# gauge-adapter.net
KiCad netlist of a schematic drawn in EAGLE
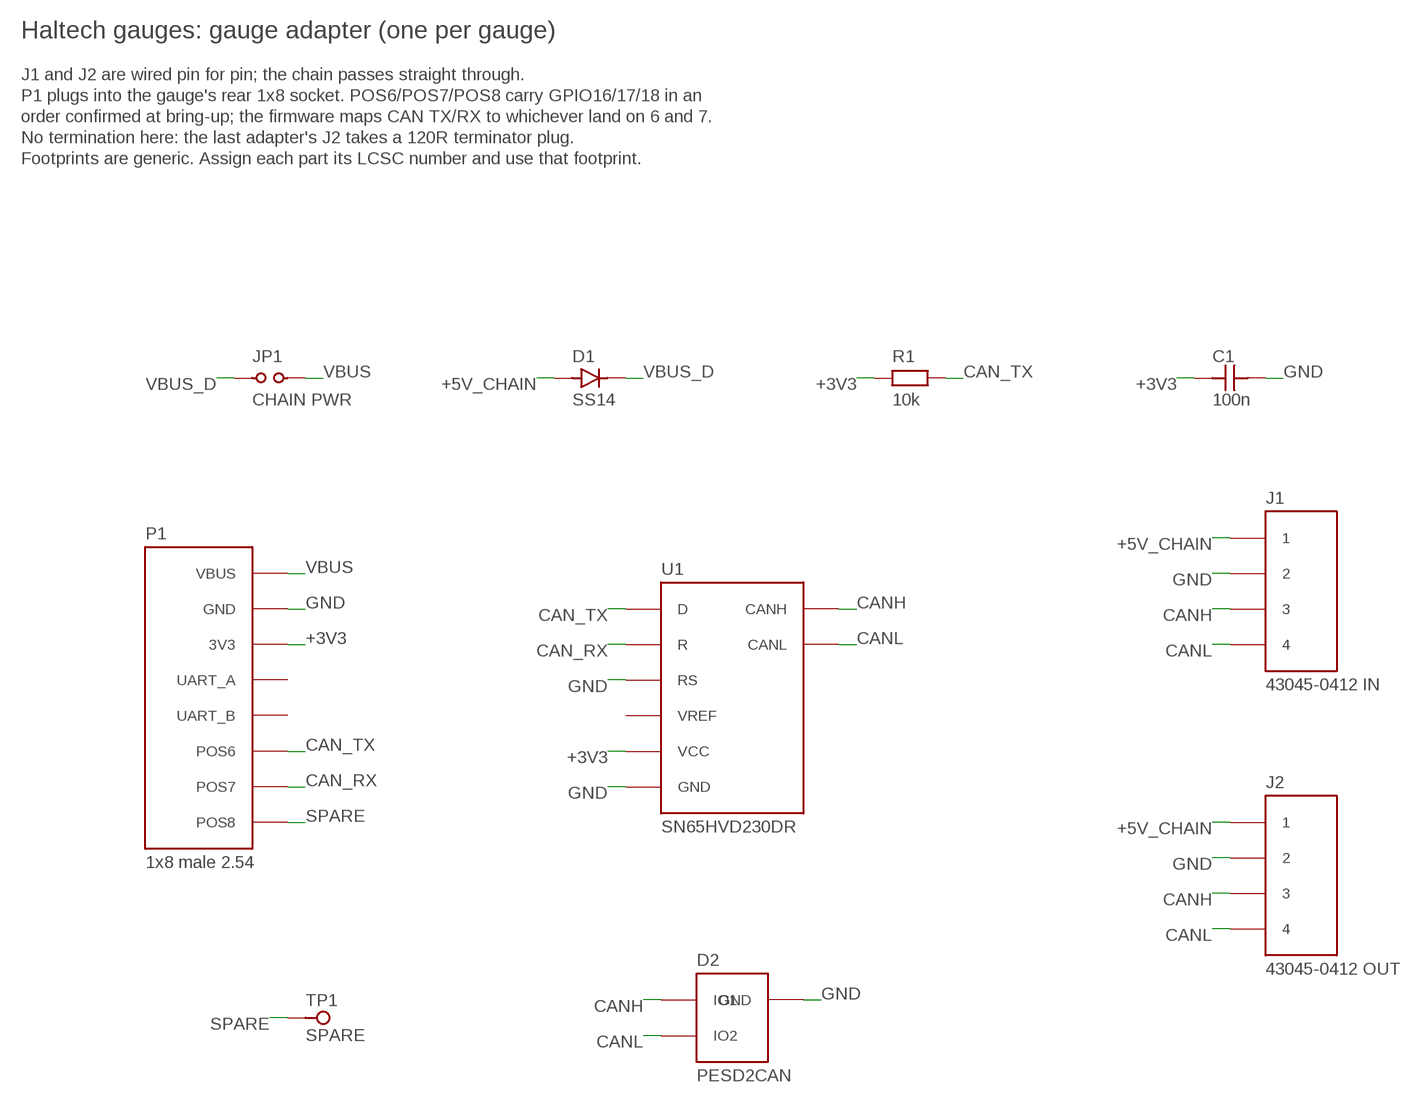
[diagram p0: schematic, sheet 1]

(export (version "E")
  (design (tool "Eeschema 10.0.6"))
  (components
    (comp (ref "C1")
      (value "100n")
      (footprint "eagle-import:0805")
      (fields (field (name "LCSC") "C49678"))
      (libsource (lib "eagle-import") (part "C0805"))
    )
    (comp (ref "D1")
      (value "SS14")
      (footprint "eagle-import:SMA")
      (fields (field (name "LCSC") "C2480"))
      (libsource (lib "eagle-import") (part "SCHOTTKY-SMA"))
    )
    (comp (ref "D2")
      (value "PESD2CAN")
      (footprint "eagle-import:SOT23")
      (fields (field (name "LCSC") "C75176"))
      (libsource (lib "eagle-import") (part "PESD2CAN"))
    )
    (comp (ref "J1")
      (value "43045-0412 IN")
      (footprint "eagle-import:MOLEX-43045-0412")
      (libsource (lib "eagle-import") (part "MICROFIT-2X2"))
    )
    (comp (ref "J2")
      (value "43045-0412 OUT")
      (footprint "eagle-import:MOLEX-43045-0412")
      (libsource (lib "eagle-import") (part "MICROFIT-2X2"))
    )
    (comp (ref "JP1")
      (value "CHAIN PWR")
      (footprint "eagle-import:HDR-1X2")
      (libsource (lib "eagle-import") (part "JUMPER-2"))
    )
    (comp (ref "P1")
      (value "1x8 male 2.54")
      (footprint "eagle-import:HDR-1X8")
      (libsource (lib "eagle-import") (part "GAUGE-HEADER"))
    )
    (comp (ref "R1")
      (value "10k")
      (footprint "eagle-import:0805")
      (fields (field (name "LCSC") "C17414"))
      (libsource (lib "eagle-import") (part "R0805"))
    )
    (comp (ref "TP1")
      (value "SPARE")
      (footprint "eagle-import:TESTPAD")
      (libsource (lib "eagle-import") (part "TESTPOINT"))
    )
    (comp (ref "U1")
      (value "SN65HVD230DR")
      (footprint "eagle-import:SOIC8")
      (fields (field (name "LCSC") "C12084"))
      (libsource (lib "eagle-import") (part "SN65HVD230"))
    )
  )
  (nets
    (net (code "1") (name "/+3V3") (class "Default")
      (node (ref "C1") (pin "1") (pinfunction "1_1") (pintype "passive"))
      (node (ref "P1") (pin "3") (pinfunction "3V3_3") (pintype "passive"))
      (node (ref "R1") (pin "1") (pinfunction "1_1") (pintype "passive"))
      (node (ref "U1") (pin "3") (pinfunction "VCC_3") (pintype "passive"))
    )
    (net (code "2") (name "/+5V_CHAIN") (class "Default")
      (node (ref "D1") (pin "2") (pinfunction "A_2") (pintype "passive"))
      (node (ref "J1") (pin "1") (pinfunction "1_1") (pintype "passive"))
      (node (ref "J2") (pin "1") (pinfunction "1_1") (pintype "passive"))
    )
    (net (code "3") (name "/CANH") (class "Default")
      (node (ref "D2") (pin "1") (pinfunction "IO1_1") (pintype "passive"))
      (node (ref "J1") (pin "3") (pinfunction "3_3") (pintype "passive"))
      (node (ref "J2") (pin "3") (pinfunction "3_3") (pintype "passive"))
      (node (ref "U1") (pin "7") (pinfunction "CANH_7") (pintype "passive"))
    )
    (net (code "4") (name "/CANL") (class "Default")
      (node (ref "D2") (pin "2") (pinfunction "IO2_2") (pintype "passive"))
      (node (ref "J1") (pin "4") (pinfunction "4_4") (pintype "passive"))
      (node (ref "J2") (pin "4") (pinfunction "4_4") (pintype "passive"))
      (node (ref "U1") (pin "6") (pinfunction "CANL_6") (pintype "passive"))
    )
    (net (code "5") (name "/CAN_RX") (class "Default")
      (node (ref "P1") (pin "7") (pinfunction "POS7_7") (pintype "passive"))
      (node (ref "U1") (pin "4") (pinfunction "R_4") (pintype "passive"))
    )
    (net (code "6") (name "/CAN_TX") (class "Default")
      (node (ref "P1") (pin "6") (pinfunction "POS6_6") (pintype "passive"))
      (node (ref "R1") (pin "2") (pinfunction "2_2") (pintype "passive"))
      (node (ref "U1") (pin "1") (pinfunction "D_1") (pintype "passive"))
    )
    (net (code "7") (name "/GND") (class "Default")
      (node (ref "C1") (pin "2") (pinfunction "2_2") (pintype "passive"))
      (node (ref "D2") (pin "3") (pinfunction "GND_3") (pintype "passive"))
      (node (ref "J1") (pin "2") (pinfunction "2_2") (pintype "passive"))
      (node (ref "J2") (pin "2") (pinfunction "2_2") (pintype "passive"))
      (node (ref "P1") (pin "2") (pinfunction "GND_2") (pintype "passive"))
      (node (ref "U1") (pin "2") (pinfunction "GND_2") (pintype "passive"))
      (node (ref "U1") (pin "8") (pinfunction "RS_8") (pintype "passive"))
    )
    (net (code "8") (name "/SPARE") (class "Default")
      (node (ref "P1") (pin "8") (pinfunction "POS8_8") (pintype "passive"))
      (node (ref "TP1") (pin "1") (pinfunction "TP_1") (pintype "passive"))
    )
    (net (code "9") (name "/VBUS") (class "Default")
      (node (ref "JP1") (pin "2") (pinfunction "2_2") (pintype "passive"))
      (node (ref "P1") (pin "1") (pinfunction "VBUS_1") (pintype "passive"))
    )
    (net (code "10") (name "/VBUS_D") (class "Default")
      (node (ref "D1") (pin "1") (pinfunction "K_1") (pintype "passive"))
      (node (ref "JP1") (pin "1") (pinfunction "1_1") (pintype "passive"))
    )
    (net (code "11") (name "unconnected-(P1-UART_A-Pad4)") (class "Default")
      (node (ref "P1") (pin "4") (pinfunction "UART_A_4") (pintype "passive"))
    )
    (net (code "12") (name "unconnected-(P1-UART_B-Pad5)") (class "Default")
      (node (ref "P1") (pin "5") (pinfunction "UART_B_5") (pintype "passive"))
    )
    (net (code "13") (name "unconnected-(U1-VREF-Pad5)") (class "Default")
      (node (ref "U1") (pin "5") (pinfunction "VREF_5") (pintype "passive"))
    )
  )
)
